# Dev.net
KiCad netlist of a schematic drawn in Altium Designer
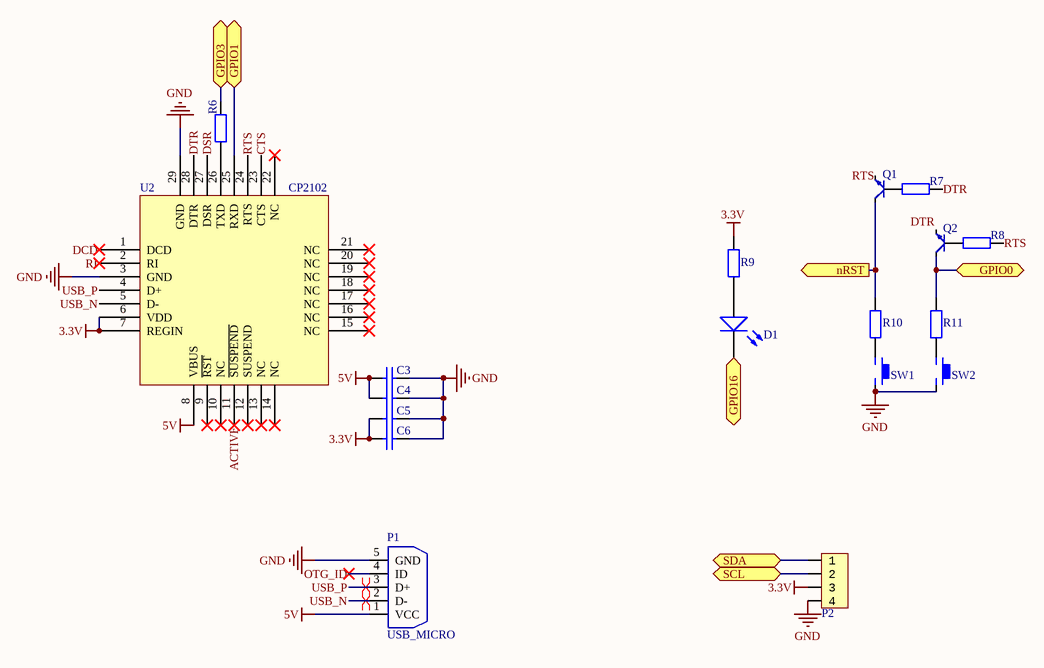
[diagram p0: Dev.SchDoc]

(export (version "E")
  (design (tool "Eeschema 10.0.6"))
  (components
    (comp (ref "C3")
      (value "100nF")
      (footprint "CAP-0603")
      (description "贴片电容")
      (libsource (lib "Power_Lib_Altium") (part "CAP"))
    )
    (comp (ref "C4")
      (value "10uF")
      (footprint "CAP-0603")
      (description "贴片电容")
      (libsource (lib "Power_Lib_Altium") (part "CAP"))
    )
    (comp (ref "C5")
      (value "100nF")
      (footprint "CAP-0603")
      (description "贴片电容")
      (libsource (lib "Power_Lib_Altium") (part "CAP"))
    )
    (comp (ref "C6")
      (value "10uF")
      (footprint "CAP-0603")
      (description "贴片电容")
      (libsource (lib "Power_Lib_Altium") (part "CAP"))
    )
    (comp (ref "D1")
      (value "BLUE")
      (footprint "LED_0603")
      (description "发光二极管")
      (libsource (lib "Power_Lib_Altium") (part "LED"))
    )
    (comp (ref "P1")
      (value "USB_MICRO")
      (footprint "MICROUSB-SOP")
      (description "USB 接口")
      (libsource (lib "Power_Lib_Altium") (part "USB_MICRO"))
    )
    (comp (ref "P2")
      (value "HDR1x4_2.54")
      (footprint "HDR1x4_2.54_180")
      (description "Header")
      (libsource (lib "Power_Lib_Altium") (part "HDR1x4_2.54"))
    )
    (comp (ref "Q1")
      (value "S8050")
      (footprint "SOT-23-3")
      (description "晶体管")
      (libsource (lib "Power_Lib_Altium") (part "BJT_NPN"))
    )
    (comp (ref "Q2")
      (value "S8050")
      (footprint "SOT-23-3")
      (description "晶体管")
      (libsource (lib "Power_Lib_Altium") (part "BJT_NPN"))
    )
    (comp (ref "R6")
      (value "470R")
      (footprint "R-0603")
      (description "贴片电阻")
      (libsource (lib "") (part "RES_1"))
    )
    (comp (ref "R7")
      (value "1R")
      (footprint "R-0603")
      (description "贴片电阻")
      (libsource (lib "Power_Lib_Altium") (part "RES"))
    )
    (comp (ref "R8")
      (value "1R")
      (footprint "R-0603")
      (description "贴片电阻")
      (libsource (lib "Power_Lib_Altium") (part "RES"))
    )
    (comp (ref "R9")
      (value "470R")
      (footprint "R-0603")
      (description "贴片电阻")
      (libsource (lib "") (part "RES_1"))
    )
    (comp (ref "R10")
      (value "470R")
      (footprint "R-0603")
      (description "贴片电阻")
      (libsource (lib "") (part "RES_1"))
    )
    (comp (ref "R11")
      (value "470R")
      (footprint "R-0603")
      (description "贴片电阻")
      (libsource (lib "") (part "RES_1"))
    )
    (comp (ref "SW1")
      (value "KEY")
      (footprint "KEY-4P-4.2*3.4*2.5")
      (description "按键开关")
      (libsource (lib "Power_Lib_Altium") (part "KEY"))
    )
    (comp (ref "SW2")
      (value "KEY")
      (footprint "KEY-4P-4.2*3.4*2.5")
      (description "按键开关")
      (libsource (lib "Power_Lib_Altium") (part "KEY"))
    )
    (comp (ref "U2")
      (value "CP2102")
      (footprint "QFN28")
      (description "USB to UART")
      (libsource (lib "Power_Lib_Altium") (part "CP2102"))
    )
  )
  (nets
    (net (code "1") (name "/ACTIVE") (class "Default")
      (node (ref "U2") (pin "11") (pinfunction "~{SUSPEND}_11") (pintype "passive+no_connect"))
    )
    (net (code "2") (name "/CTS") (class "Default")
      (node (ref "U2") (pin "23") (pinfunction "CTS_23") (pintype "passive"))
    )
    (net (code "3") (name "/DCD") (class "Default")
      (node (ref "U2") (pin "1") (pinfunction "DCD_1") (pintype "passive+no_connect"))
    )
    (net (code "4") (name "/DSR") (class "Default")
      (node (ref "U2") (pin "27") (pinfunction "DSR_27") (pintype "passive"))
    )
    (net (code "5") (name "/DTR") (class "Default")
      (node (ref "Q2") (pin "2") (pinfunction "E_2") (pintype "passive"))
      (node (ref "R7") (pin "2") (pinfunction "2_2") (pintype "passive"))
      (node (ref "U2") (pin "28") (pinfunction "DTR_28") (pintype "passive"))
    )
    (net (code "6") (name "/GPIO0") (class "Default")
      (node (ref "Q2") (pin "3") (pinfunction "C_3") (pintype "passive"))
      (node (ref "R11") (pin "2") (pinfunction "2_2") (pintype "passive"))
    )
    (net (code "7") (name "/GPIO1") (class "Default")
      (node (ref "U2") (pin "25") (pinfunction "RXD_25") (pintype "passive"))
    )
    (net (code "8") (name "/GPIO3") (class "Default")
      (node (ref "R6") (pin "2") (pinfunction "2_2") (pintype "passive"))
    )
    (net (code "9") (name "/GPIO16") (class "Default")
      (node (ref "D1") (pin "K") (pinfunction "K_K") (pintype "passive"))
    )
    (net (code "10") (name "/OTG_ID") (class "Default")
      (node (ref "P1") (pin "4") (pinfunction "ID_4") (pintype "passive+no_connect"))
    )
    (net (code "11") (name "/RI") (class "Default")
      (node (ref "U2") (pin "2") (pinfunction "RI_2") (pintype "passive+no_connect"))
    )
    (net (code "12") (name "/RTS") (class "Default")
      (node (ref "Q1") (pin "2") (pinfunction "E_2") (pintype "passive"))
      (node (ref "R8") (pin "2") (pinfunction "2_2") (pintype "passive"))
      (node (ref "U2") (pin "24") (pinfunction "RTS_24") (pintype "passive"))
    )
    (net (code "13") (name "/SCL") (class "Default")
      (node (ref "P2") (pin "2") (pinfunction "2_2") (pintype "passive"))
    )
    (net (code "14") (name "/SDA") (class "Default")
      (node (ref "P2") (pin "1") (pinfunction "1_1") (pintype "passive"))
    )
    (net (code "15") (name "/USB_N") (class "Default")
      (node (ref "P1") (pin "2") (pinfunction "D-_2") (pintype "passive"))
      (node (ref "U2") (pin "5") (pinfunction "D-_5") (pintype "passive"))
    )
    (net (code "16") (name "/USB_P") (class "Default")
      (node (ref "P1") (pin "3") (pinfunction "D+_3") (pintype "passive"))
      (node (ref "U2") (pin "4") (pinfunction "D+_4") (pintype "passive"))
    )
    (net (code "17") (name "/nRST") (class "Default")
      (node (ref "Q1") (pin "3") (pinfunction "C_3") (pintype "passive"))
      (node (ref "R10") (pin "2") (pinfunction "2_2") (pintype "passive"))
    )
    (net (code "18") (name "3.3V") (class "Default")
      (node (ref "C5") (pin "1") (pinfunction "1_1") (pintype "passive"))
      (node (ref "C6") (pin "1") (pinfunction "1_1") (pintype "passive"))
      (node (ref "P2") (pin "3") (pinfunction "3_3") (pintype "passive"))
      (node (ref "R9") (pin "2") (pinfunction "2_2") (pintype "passive"))
      (node (ref "U2") (pin "6") (pinfunction "VDD_6") (pintype "passive"))
      (node (ref "U2") (pin "7") (pinfunction "REGIN_7") (pintype "passive"))
    )
    (net (code "19") (name "5V") (class "Default")
      (node (ref "C3") (pin "1") (pinfunction "1_1") (pintype "passive"))
      (node (ref "C4") (pin "1") (pinfunction "1_1") (pintype "passive"))
      (node (ref "P1") (pin "1") (pinfunction "VCC_1") (pintype "passive"))
      (node (ref "U2") (pin "8") (pinfunction "VBUS_8") (pintype "passive"))
    )
    (net (code "20") (name "GND") (class "Default")
      (node (ref "C3") (pin "2") (pinfunction "2_2") (pintype "passive"))
      (node (ref "C4") (pin "2") (pinfunction "2_2") (pintype "passive"))
      (node (ref "C5") (pin "2") (pinfunction "2_2") (pintype "passive"))
      (node (ref "C6") (pin "2") (pinfunction "2_2") (pintype "passive"))
      (node (ref "P1") (pin "5") (pinfunction "GND_5") (pintype "passive"))
      (node (ref "P2") (pin "4") (pinfunction "4_4") (pintype "passive"))
      (node (ref "SW1") (pin "2") (pinfunction "2_2") (pintype "passive"))
      (node (ref "SW2") (pin "2") (pinfunction "2_2") (pintype "passive"))
      (node (ref "U2") (pin "29") (pinfunction "GND_29") (pintype "passive"))
      (node (ref "U2") (pin "3") (pinfunction "GND_3") (pintype "passive"))
    )
    (net (code "21") (name "Net-(D1-PadA)") (class "Default")
      (node (ref "D1") (pin "A") (pinfunction "A_A") (pintype "passive"))
      (node (ref "R9") (pin "1") (pinfunction "1_1") (pintype "passive"))
    )
    (net (code "22") (name "Net-(Q1-B)") (class "Default")
      (node (ref "Q1") (pin "1") (pinfunction "B_1") (pintype "passive"))
      (node (ref "R7") (pin "1") (pinfunction "1_1") (pintype "passive"))
    )
    (net (code "23") (name "Net-(Q2-B)") (class "Default")
      (node (ref "Q2") (pin "1") (pinfunction "B_1") (pintype "passive"))
      (node (ref "R8") (pin "1") (pinfunction "1_1") (pintype "passive"))
    )
    (net (code "24") (name "Net-(R10-Pad1)") (class "Default")
      (node (ref "R10") (pin "1") (pinfunction "1_1") (pintype "passive"))
      (node (ref "SW1") (pin "1") (pinfunction "1_1") (pintype "passive"))
    )
    (net (code "25") (name "Net-(R11-Pad1)") (class "Default")
      (node (ref "R11") (pin "1") (pinfunction "1_1") (pintype "passive"))
      (node (ref "SW2") (pin "1") (pinfunction "1_1") (pintype "passive"))
    )
    (net (code "26") (name "Net-(U2-TXD)") (class "Default")
      (node (ref "R6") (pin "1") (pinfunction "1_1") (pintype "passive"))
      (node (ref "U2") (pin "26") (pinfunction "TXD_26") (pintype "passive"))
    )
    (net (code "27") (name "unconnected-(U2-NC-Pad10)") (class "Default")
      (node (ref "U2") (pin "10") (pinfunction "NC_10") (pintype "passive+no_connect"))
    )
    (net (code "28") (name "unconnected-(U2-NC-Pad13)") (class "Default")
      (node (ref "U2") (pin "13") (pinfunction "NC_13") (pintype "passive+no_connect"))
    )
    (net (code "29") (name "unconnected-(U2-NC-Pad14)") (class "Default")
      (node (ref "U2") (pin "14") (pinfunction "NC_14") (pintype "passive+no_connect"))
    )
    (net (code "30") (name "unconnected-(U2-NC-Pad15)") (class "Default")
      (node (ref "U2") (pin "15") (pinfunction "NC_15") (pintype "passive+no_connect"))
    )
    (net (code "31") (name "unconnected-(U2-NC-Pad16)") (class "Default")
      (node (ref "U2") (pin "16") (pinfunction "NC_16") (pintype "passive+no_connect"))
    )
    (net (code "32") (name "unconnected-(U2-NC-Pad17)") (class "Default")
      (node (ref "U2") (pin "17") (pinfunction "NC_17") (pintype "passive+no_connect"))
    )
    (net (code "33") (name "unconnected-(U2-NC-Pad18)") (class "Default")
      (node (ref "U2") (pin "18") (pinfunction "NC_18") (pintype "passive+no_connect"))
    )
    (net (code "34") (name "unconnected-(U2-NC-Pad19)") (class "Default")
      (node (ref "U2") (pin "19") (pinfunction "NC_19") (pintype "passive+no_connect"))
    )
    (net (code "35") (name "unconnected-(U2-NC-Pad20)") (class "Default")
      (node (ref "U2") (pin "20") (pinfunction "NC_20") (pintype "passive+no_connect"))
    )
    (net (code "36") (name "unconnected-(U2-NC-Pad21)") (class "Default")
      (node (ref "U2") (pin "21") (pinfunction "NC_21") (pintype "passive+no_connect"))
    )
    (net (code "37") (name "unconnected-(U2-NC-Pad22)") (class "Default")
      (node (ref "U2") (pin "22") (pinfunction "NC_22") (pintype "passive+no_connect"))
    )
    (net (code "38") (name "unconnected-(U2-SUSPEND-Pad12)") (class "Default")
      (node (ref "U2") (pin "12") (pinfunction "SUSPEND_12") (pintype "passive+no_connect"))
    )
    (net (code "39") (name "unconnected-(U2-~{RST}-Pad9)") (class "Default")
      (node (ref "U2") (pin "9") (pinfunction "~{RST}_9") (pintype "passive+no_connect"))
    )
  )
)
